# Sheet1_Young.net
KiCad netlist of a schematic drawn in Altium Designer
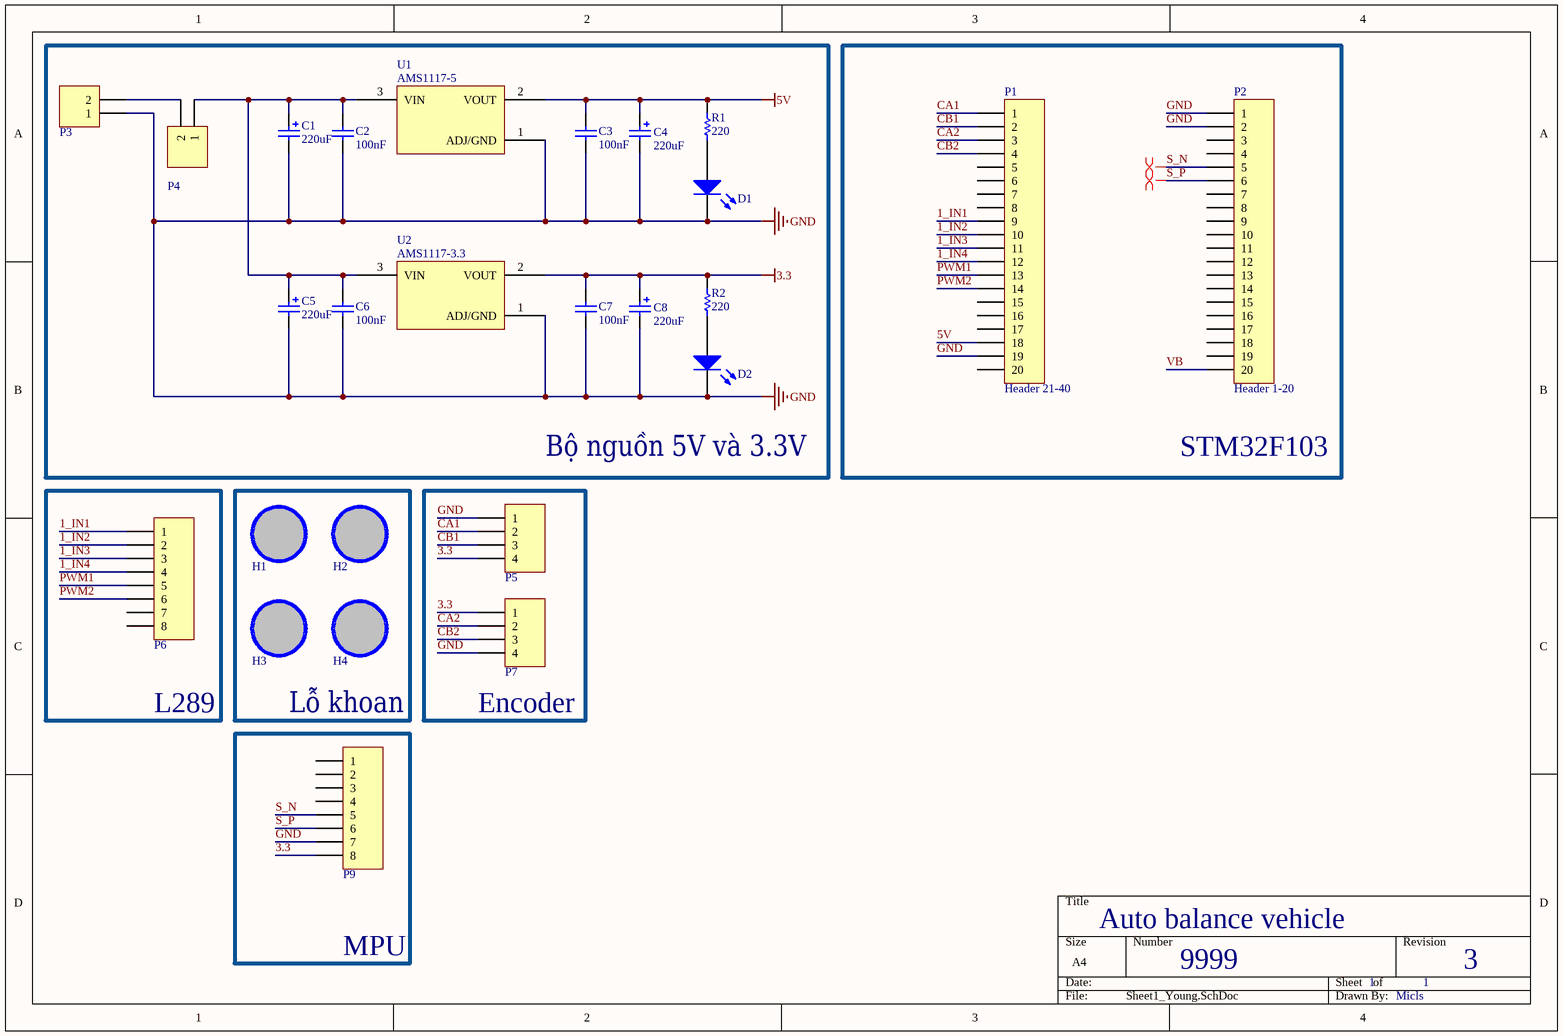
[diagram p0: Sheet1_Young.SchDoc]

(export (version "E")
  (design (tool "Eeschema 10.0.6"))
  (components
    (comp (ref "C1")
      (value "220uF")
      (footprint "CAP ALU SIZE B")
      (description "Polarized Capacitor (Radial)")
      (fields (field (name "Comment") "Cap Pol SMD"))
      (libsource (lib "PIF_Library") (part "Cap Pol SMD"))
    )
    (comp (ref "C2")
      (value "100nF")
      (footprint "CAP-SM-0805")
      (description "Capacitor")
      (fields (field (name "Comment") "Cap Non-Pol SMD"))
      (libsource (lib "PIF_Library") (part "Cap Non-Pol SMD"))
    )
    (comp (ref "C3")
      (value "100nF")
      (footprint "CAP-SM-0805")
      (description "Capacitor")
      (fields (field (name "Comment") "Cap Non-Pol SMD"))
      (libsource (lib "PIF_Library") (part "Cap Non-Pol SMD"))
    )
    (comp (ref "C4")
      (value "220uF")
      (footprint "CAP ALU SIZE B")
      (description "Polarized Capacitor (Radial)")
      (fields (field (name "Comment") "Cap Pol SMD"))
      (libsource (lib "PIF_Library") (part "Cap Pol SMD"))
    )
    (comp (ref "C5")
      (value "220uF")
      (footprint "CAP ALU SIZE B")
      (description "Polarized Capacitor (Radial)")
      (fields (field (name "Comment") "Cap Pol SMD"))
      (libsource (lib "PIF_Library") (part "Cap Pol SMD"))
    )
    (comp (ref "C6")
      (value "100nF")
      (footprint "CAP-SM-0805")
      (description "Capacitor")
      (fields (field (name "Comment") "Cap Non-Pol SMD"))
      (libsource (lib "PIF_Library") (part "Cap Non-Pol SMD"))
    )
    (comp (ref "C7")
      (value "100nF")
      (footprint "CAP-SM-0805")
      (description "Capacitor")
      (fields (field (name "Comment") "Cap Non-Pol SMD"))
      (libsource (lib "PIF_Library") (part "Cap Non-Pol SMD"))
    )
    (comp (ref "C8")
      (value "220uF")
      (footprint "CAP ALU SIZE B")
      (description "Polarized Capacitor (Radial)")
      (fields (field (name "Comment") "Cap Pol SMD"))
      (libsource (lib "PIF_Library") (part "Cap Pol SMD"))
    )
    (comp (ref "D1")
      (value "LED SMD")
      (footprint "LED_0805_Blue")
      (description "LED")
      (libsource (lib "PIF_Library") (part "LED SMD"))
    )
    (comp (ref "D2")
      (value "LED SMD")
      (footprint "LED_0805_Blue")
      (description "LED")
      (libsource (lib "PIF_Library") (part "LED SMD"))
    )
    (comp (ref "H1")
      (value "Hole")
      (footprint "LO KHOAN 3MM")
      (description "Hole 3mm")
      (libsource (lib "PIF_Library") (part "Hole"))
    )
    (comp (ref "H2")
      (value "Hole")
      (footprint "LO KHOAN 3MM")
      (description "Hole 3mm")
      (libsource (lib "PIF_Library") (part "Hole"))
    )
    (comp (ref "H3")
      (value "Hole")
      (footprint "LO KHOAN 3MM")
      (description "Hole 3mm")
      (libsource (lib "PIF_Library") (part "Hole"))
    )
    (comp (ref "H4")
      (value "Hole")
      (footprint "LO KHOAN 3MM")
      (description "Hole 3mm")
      (libsource (lib "PIF_Library") (part "Hole"))
    )
    (comp (ref "P1")
      (value "Header 21-40")
      (footprint "HDR1X20")
      (description "Header, 20-Pin")
      (fields (field (name "PUBLISHER") "Altium Limited"))
      (libsource (lib "Miscellaneous Connectors") (part "Header 20"))
    )
    (comp (ref "P2")
      (value "Header 1-20")
      (footprint "HDR1X20")
      (description "Header, 20-Pin")
      (fields (field (name "PUBLISHER") "Altium Limited"))
      (libsource (lib "Miscellaneous Connectors") (part "Header 20"))
    )
    (comp (ref "P3")
      (value "Domino 2")
      (footprint "DOMINO 2- 5mm")
      (description "Domino, 2-Pin")
      (fields (field (name "PUBLISHER") "Altium Limited"))
      (libsource (lib "") (part "Domino 2_1"))
    )
    (comp (ref "P4")
      (value "Domino 2")
      (footprint "DOMINO 2- 5mm")
      (description "Domino, 2-Pin")
      (fields (field (name "PUBLISHER") "Altium Limited"))
      (libsource (lib "PIF_Library") (part "Domino 2"))
    )
    (comp (ref "P5")
      (value "Header 4")
      (footprint "JP4")
      (description "Header, 4-Pin")
      (fields (field (name "PUBLISHER") "Altium Limited"))
      (libsource (lib "PIF_Library") (part "Header 4"))
    )
    (comp (ref "P6")
      (value "Header 8")
      (footprint "JP8")
      (description "Header, 8-Pin")
      (fields (field (name "PUBLISHER") "Altium Limited"))
      (libsource (lib "PIF_Library") (part "Header 8"))
    )
    (comp (ref "P7")
      (value "Header 4")
      (footprint "JP4")
      (description "Header, 4-Pin")
      (fields (field (name "PUBLISHER") "Altium Limited"))
      (libsource (lib "PIF_Library") (part "Header 4"))
    )
    (comp (ref "P9")
      (value "Header 8")
      (footprint "JP8")
      (description "Header, 8-Pin")
      (fields (field (name "PUBLISHER") "Altium Limited"))
      (libsource (lib "PIF_Library") (part "Header 8"))
    )
    (comp (ref "R1")
      (value "220")
      (footprint "RES-SM-0805")
      (description "Resistor")
      (fields (field (name "Comment") "RESISTOR SMD"))
      (libsource (lib "PIF_Library") (part "RESISTOR SMD"))
    )
    (comp (ref "R2")
      (value "220")
      (footprint "RES-SM-0805")
      (description "Resistor")
      (fields (field (name "Comment") "RESISTOR SMD"))
      (libsource (lib "PIF_Library") (part "RESISTOR SMD"))
    )
    (comp (ref "U1")
      (value "AMS1117-5")
      (footprint "SOT230P700X180-4N")
      (fields (field (name "MP") "AMS1117-3.3") (field (name "MF") "NEC"))
      (libsource (lib "AMS1117-3.3") (part "AMS1117-3.3"))
    )
    (comp (ref "U2")
      (value "AMS1117-3.3")
      (footprint "SOT230P700X180-4N")
      (fields (field (name "MF") "NEC"))
      (libsource (lib "AMS1117-3.3") (part "AMS1117-3.3"))
    )
  )
  (nets
    (net (code "1") (name "/1_IN1") (class "Default")
      (node (ref "P1") (pin "9") (pinfunction "9_9") (pintype "passive"))
      (node (ref "P6") (pin "1") (pinfunction "1_1") (pintype "passive"))
    )
    (net (code "2") (name "/1_IN2") (class "Default")
      (node (ref "P1") (pin "10") (pinfunction "10_10") (pintype "passive"))
      (node (ref "P6") (pin "2") (pinfunction "2_2") (pintype "passive"))
    )
    (net (code "3") (name "/1_IN3") (class "Default")
      (node (ref "P1") (pin "11") (pinfunction "11_11") (pintype "passive"))
      (node (ref "P6") (pin "3") (pinfunction "3_3") (pintype "passive"))
    )
    (net (code "4") (name "/1_IN4") (class "Default")
      (node (ref "P1") (pin "12") (pinfunction "12_12") (pintype "passive"))
      (node (ref "P6") (pin "4") (pinfunction "4_4") (pintype "passive"))
    )
    (net (code "5") (name "/CA1") (class "Default")
      (node (ref "P1") (pin "1") (pinfunction "1_1") (pintype "passive"))
      (node (ref "P5") (pin "2") (pinfunction "2_2") (pintype "passive"))
    )
    (net (code "6") (name "/CA2") (class "Default")
      (node (ref "P1") (pin "3") (pinfunction "3_3") (pintype "passive"))
      (node (ref "P7") (pin "2") (pinfunction "2_2") (pintype "passive"))
    )
    (net (code "7") (name "/CB1") (class "Default")
      (node (ref "P1") (pin "2") (pinfunction "2_2") (pintype "passive"))
      (node (ref "P5") (pin "3") (pinfunction "3_3") (pintype "passive"))
    )
    (net (code "8") (name "/CB2") (class "Default")
      (node (ref "P1") (pin "4") (pinfunction "4_4") (pintype "passive"))
      (node (ref "P7") (pin "3") (pinfunction "3_3") (pintype "passive"))
    )
    (net (code "9") (name "/PWM1") (class "Default")
      (node (ref "P1") (pin "13") (pinfunction "13_13") (pintype "passive"))
      (node (ref "P6") (pin "5") (pinfunction "5_5") (pintype "passive"))
    )
    (net (code "10") (name "/PWM2") (class "Default")
      (node (ref "P1") (pin "14") (pinfunction "14_14") (pintype "passive"))
      (node (ref "P6") (pin "6") (pinfunction "6_6") (pintype "passive"))
    )
    (net (code "11") (name "/S_N") (class "Default")
      (node (ref "P2") (pin "5") (pinfunction "5_5") (pintype "passive"))
      (node (ref "P9") (pin "5") (pinfunction "5_5") (pintype "passive"))
    )
    (net (code "12") (name "/S_P") (class "Default")
      (node (ref "P2") (pin "6") (pinfunction "6_6") (pintype "passive"))
      (node (ref "P9") (pin "6") (pinfunction "6_6") (pintype "passive"))
    )
    (net (code "13") (name "/VB") (class "Default")
      (node (ref "P2") (pin "20") (pinfunction "20_20") (pintype "passive"))
    )
    (net (code "14") (name "3.3") (class "Default")
      (node (ref "C7") (pin "1") (pinfunction "1_1") (pintype "passive"))
      (node (ref "C8") (pin "1") (pinfunction "1_1") (pintype "passive"))
      (node (ref "P5") (pin "4") (pinfunction "4_4") (pintype "passive"))
      (node (ref "P7") (pin "1") (pinfunction "1_1") (pintype "passive"))
      (node (ref "P9") (pin "8") (pinfunction "8_8") (pintype "passive"))
      (node (ref "R2") (pin "2") (pinfunction "2_2") (pintype "passive"))
      (node (ref "U2") (pin "2") (pinfunction "VOUT_2") (pintype "passive"))
    )
    (net (code "15") (name "5V") (class "Default")
      (node (ref "C3") (pin "1") (pinfunction "1_1") (pintype "passive"))
      (node (ref "C4") (pin "1") (pinfunction "1_1") (pintype "passive"))
      (node (ref "P1") (pin "18") (pinfunction "18_18") (pintype "passive"))
      (node (ref "R1") (pin "2") (pinfunction "2_2") (pintype "passive"))
      (node (ref "U1") (pin "2") (pinfunction "VOUT_2") (pintype "passive"))
    )
    (net (code "16") (name "GND") (class "Default")
      (node (ref "C1") (pin "2") (pinfunction "2_2") (pintype "passive"))
      (node (ref "C2") (pin "1") (pinfunction "1_1") (pintype "passive"))
      (node (ref "C3") (pin "2") (pinfunction "2_2") (pintype "passive"))
      (node (ref "C4") (pin "2") (pinfunction "2_2") (pintype "passive"))
      (node (ref "C5") (pin "2") (pinfunction "2_2") (pintype "passive"))
      (node (ref "C6") (pin "1") (pinfunction "1_1") (pintype "passive"))
      (node (ref "C7") (pin "2") (pinfunction "2_2") (pintype "passive"))
      (node (ref "C8") (pin "2") (pinfunction "2_2") (pintype "passive"))
      (node (ref "D1") (pin "2") (pinfunction "K_2") (pintype "passive"))
      (node (ref "D2") (pin "2") (pinfunction "K_2") (pintype "passive"))
      (node (ref "P1") (pin "19") (pinfunction "19_19") (pintype "passive"))
      (node (ref "P2") (pin "1") (pinfunction "1_1") (pintype "passive"))
      (node (ref "P2") (pin "2") (pinfunction "2_2") (pintype "passive"))
      (node (ref "P3") (pin "1") (pinfunction "1_1") (pintype "passive"))
      (node (ref "P5") (pin "1") (pinfunction "1_1") (pintype "passive"))
      (node (ref "P7") (pin "4") (pinfunction "4_4") (pintype "passive"))
      (node (ref "P9") (pin "7") (pinfunction "7_7") (pintype "passive"))
      (node (ref "U1") (pin "1") (pinfunction "ADJ/GND_1") (pintype "passive"))
      (node (ref "U2") (pin "1") (pinfunction "ADJ/GND_1") (pintype "passive"))
    )
    (net (code "17") (name "Net-(D1-A)") (class "Default")
      (node (ref "D1") (pin "1") (pinfunction "A_1") (pintype "passive"))
      (node (ref "R1") (pin "1") (pinfunction "1_1") (pintype "passive"))
    )
    (net (code "18") (name "Net-(D2-A)") (class "Default")
      (node (ref "D2") (pin "1") (pinfunction "A_1") (pintype "passive"))
      (node (ref "R2") (pin "1") (pinfunction "1_1") (pintype "passive"))
    )
    (net (code "19") (name "Net-(P3-Pad2)") (class "Default")
      (node (ref "P3") (pin "2") (pinfunction "2_2") (pintype "passive"))
      (node (ref "P4") (pin "2") (pinfunction "2_2") (pintype "passive"))
    )
    (net (code "20") (name "Net-(U1-VIN)") (class "Default")
      (node (ref "C1") (pin "1") (pinfunction "1_1") (pintype "passive"))
      (node (ref "C2") (pin "2") (pinfunction "2_2") (pintype "passive"))
      (node (ref "C5") (pin "1") (pinfunction "1_1") (pintype "passive"))
      (node (ref "C6") (pin "2") (pinfunction "2_2") (pintype "passive"))
      (node (ref "P4") (pin "1") (pinfunction "1_1") (pintype "passive"))
      (node (ref "U1") (pin "3") (pinfunction "VIN_3") (pintype "passive"))
      (node (ref "U2") (pin "3") (pinfunction "VIN_3") (pintype "passive"))
    )
    (net (code "21") (name "unconnected-(H1-Pad1)") (class "Default")
      (node (ref "H1") (pin "1") (pinfunction "1_1") (pintype "passive"))
    )
    (net (code "22") (name "unconnected-(H2-Pad1)") (class "Default")
      (node (ref "H2") (pin "1") (pinfunction "1_1") (pintype "passive"))
    )
    (net (code "23") (name "unconnected-(H3-Pad1)") (class "Default")
      (node (ref "H3") (pin "1") (pinfunction "1_1") (pintype "passive"))
    )
    (net (code "24") (name "unconnected-(H4-Pad1)") (class "Default")
      (node (ref "H4") (pin "1") (pinfunction "1_1") (pintype "passive"))
    )
    (net (code "25") (name "unconnected-(P1-Pad5)") (class "Default")
      (node (ref "P1") (pin "5") (pinfunction "5_5") (pintype "passive"))
    )
    (net (code "26") (name "unconnected-(P1-Pad6)") (class "Default")
      (node (ref "P1") (pin "6") (pinfunction "6_6") (pintype "passive"))
    )
    (net (code "27") (name "unconnected-(P1-Pad7)") (class "Default")
      (node (ref "P1") (pin "7") (pinfunction "7_7") (pintype "passive"))
    )
    (net (code "28") (name "unconnected-(P1-Pad8)") (class "Default")
      (node (ref "P1") (pin "8") (pinfunction "8_8") (pintype "passive"))
    )
    (net (code "29") (name "unconnected-(P1-Pad15)") (class "Default")
      (node (ref "P1") (pin "15") (pinfunction "15_15") (pintype "passive"))
    )
    (net (code "30") (name "unconnected-(P1-Pad16)") (class "Default")
      (node (ref "P1") (pin "16") (pinfunction "16_16") (pintype "passive"))
    )
    (net (code "31") (name "unconnected-(P1-Pad17)") (class "Default")
      (node (ref "P1") (pin "17") (pinfunction "17_17") (pintype "passive"))
    )
    (net (code "32") (name "unconnected-(P1-Pad20)") (class "Default")
      (node (ref "P1") (pin "20") (pinfunction "20_20") (pintype "passive"))
    )
    (net (code "33") (name "unconnected-(P2-Pad3)") (class "Default")
      (node (ref "P2") (pin "3") (pinfunction "3_3") (pintype "passive"))
    )
    (net (code "34") (name "unconnected-(P2-Pad4)") (class "Default")
      (node (ref "P2") (pin "4") (pinfunction "4_4") (pintype "passive"))
    )
    (net (code "35") (name "unconnected-(P2-Pad7)") (class "Default")
      (node (ref "P2") (pin "7") (pinfunction "7_7") (pintype "passive"))
    )
    (net (code "36") (name "unconnected-(P2-Pad8)") (class "Default")
      (node (ref "P2") (pin "8") (pinfunction "8_8") (pintype "passive"))
    )
    (net (code "37") (name "unconnected-(P2-Pad9)") (class "Default")
      (node (ref "P2") (pin "9") (pinfunction "9_9") (pintype "passive"))
    )
    (net (code "38") (name "unconnected-(P2-Pad10)") (class "Default")
      (node (ref "P2") (pin "10") (pinfunction "10_10") (pintype "passive"))
    )
    (net (code "39") (name "unconnected-(P2-Pad11)") (class "Default")
      (node (ref "P2") (pin "11") (pinfunction "11_11") (pintype "passive"))
    )
    (net (code "40") (name "unconnected-(P2-Pad12)") (class "Default")
      (node (ref "P2") (pin "12") (pinfunction "12_12") (pintype "passive"))
    )
    (net (code "41") (name "unconnected-(P2-Pad13)") (class "Default")
      (node (ref "P2") (pin "13") (pinfunction "13_13") (pintype "passive"))
    )
    (net (code "42") (name "unconnected-(P2-Pad14)") (class "Default")
      (node (ref "P2") (pin "14") (pinfunction "14_14") (pintype "passive"))
    )
    (net (code "43") (name "unconnected-(P2-Pad15)") (class "Default")
      (node (ref "P2") (pin "15") (pinfunction "15_15") (pintype "passive"))
    )
    (net (code "44") (name "unconnected-(P2-Pad16)") (class "Default")
      (node (ref "P2") (pin "16") (pinfunction "16_16") (pintype "passive"))
    )
    (net (code "45") (name "unconnected-(P2-Pad17)") (class "Default")
      (node (ref "P2") (pin "17") (pinfunction "17_17") (pintype "passive"))
    )
    (net (code "46") (name "unconnected-(P2-Pad18)") (class "Default")
      (node (ref "P2") (pin "18") (pinfunction "18_18") (pintype "passive"))
    )
    (net (code "47") (name "unconnected-(P2-Pad19)") (class "Default")
      (node (ref "P2") (pin "19") (pinfunction "19_19") (pintype "passive"))
    )
    (net (code "48") (name "unconnected-(P6-Pad7)") (class "Default")
      (node (ref "P6") (pin "7") (pinfunction "7_7") (pintype "passive"))
    )
    (net (code "49") (name "unconnected-(P6-Pad8)") (class "Default")
      (node (ref "P6") (pin "8") (pinfunction "8_8") (pintype "passive"))
    )
    (net (code "50") (name "unconnected-(P9-Pad1)") (class "Default")
      (node (ref "P9") (pin "1") (pinfunction "1_1") (pintype "passive"))
    )
    (net (code "51") (name "unconnected-(P9-Pad2)") (class "Default")
      (node (ref "P9") (pin "2") (pinfunction "2_2") (pintype "passive"))
    )
    (net (code "52") (name "unconnected-(P9-Pad3)") (class "Default")
      (node (ref "P9") (pin "3") (pinfunction "3_3") (pintype "passive"))
    )
    (net (code "53") (name "unconnected-(P9-Pad4)") (class "Default")
      (node (ref "P9") (pin "4") (pinfunction "4_4") (pintype "passive"))
    )
  )
)
